# Schematic_F450.net
KiCad netlist of a schematic drawn in Altium Designer
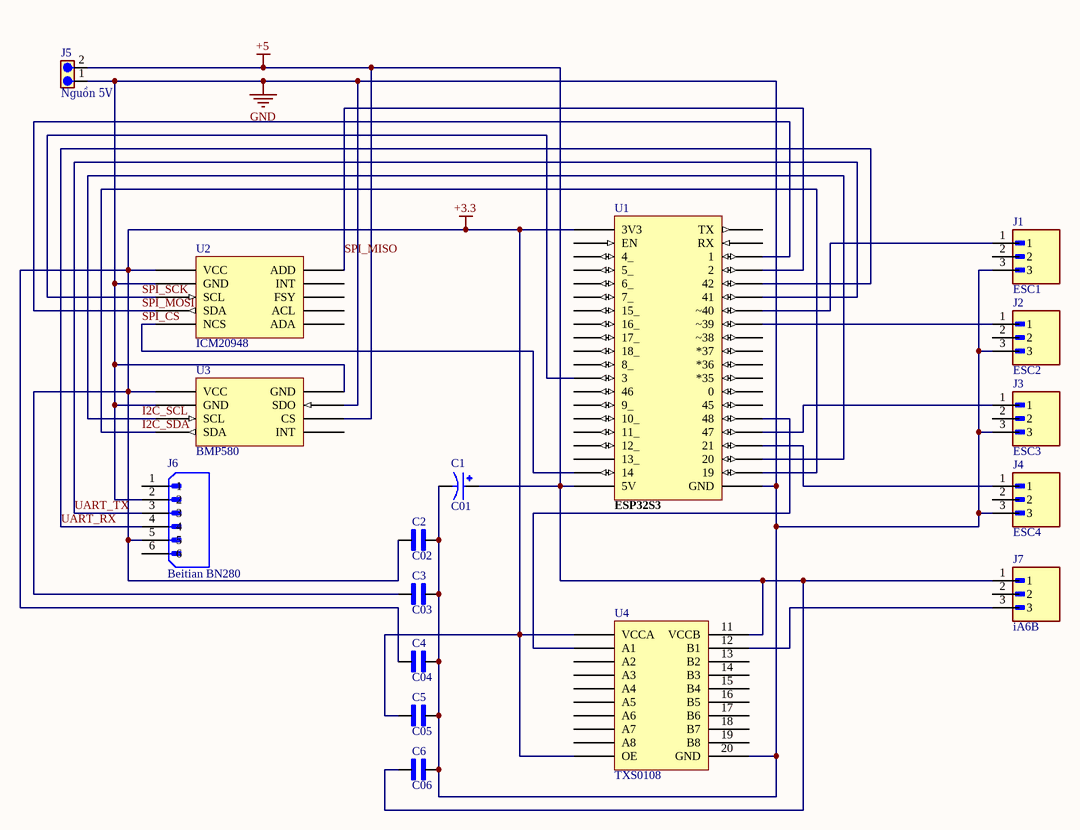
[diagram p0: Schematic F450.SchDoc]

(export (version "E")
  (design (tool "Eeschema 10.0.6"))
  (components
    (comp (ref "C1")
      (value "C01")
      (footprint "CAPPRD500W60D1000H1250")
      (description "CAP ALUM 470UF 20% 25V RADIAL TH")
      (fields (field (name "MP") "EEUFK1E471B") (field (name "MF") "Panasonic"))
      (libsource (lib "Tu Hoa 470uF") (part "EEUFK1E471B"))
    )
    (comp (ref "C2")
      (value "C02")
      (footprint "CAPRR254W54L381T254H466")
      (fields (field (name "MF") "KEMET") (field (name "MP") "C315C104K1R5TA"))
      (libsource (lib "Tu Gom 100nF") (part "C315C104K1R5TA"))
    )
    (comp (ref "C3")
      (value "C03")
      (footprint "CAPRR254W54L381T254H466")
      (fields (field (name "MF") "KEMET") (field (name "MP") "C315C104K1R5TA"))
      (libsource (lib "Tu Gom 100nF") (part "C315C104K1R5TA"))
    )
    (comp (ref "C4")
      (value "C04")
      (footprint "CAPRR254W54L381T254H466")
      (fields (field (name "MF") "KEMET") (field (name "MP") "C315C104K1R5TA"))
      (libsource (lib "Tu Gom 100nF") (part "C315C104K1R5TA"))
    )
    (comp (ref "C5")
      (value "C05")
      (footprint "CAPRR254W54L381T254H466")
      (fields (field (name "MF") "KEMET") (field (name "MP") "C315C104K1R5TA"))
      (libsource (lib "Tu Gom 100nF") (part "C315C104K1R5TA"))
    )
    (comp (ref "C6")
      (value "C06")
      (footprint "CAPRR254W54L381T254H466")
      (fields (field (name "MF") "KEMET") (field (name "MP") "C315C104K1R5TA"))
      (libsource (lib "Tu Gom 100nF") (part "C315C104K1R5TA"))
    )
    (comp (ref "J1")
      (value "ESC1")
      (footprint "WURTH_61300311121")
      (fields (field (name "MP") "61300311121"))
      (libsource (lib "Male3Pin") (part "61300311121"))
    )
    (comp (ref "J2")
      (value "ESC2")
      (footprint "WURTH_61300311121")
      (fields (field (name "MP") "61300311121"))
      (libsource (lib "Male3Pin") (part "61300311121"))
    )
    (comp (ref "J3")
      (value "ESC3")
      (footprint "WURTH_61300311121")
      (fields (field (name "MP") "61300311121"))
      (libsource (lib "Male3Pin") (part "61300311121"))
    )
    (comp (ref "J4")
      (value "ESC4")
      (footprint "WURTH_61300311121")
      (fields (field (name "MP") "61300311121"))
      (libsource (lib "Male3Pin") (part "61300311121"))
    )
    (comp (ref "J5")
      (value "Nguồn 5V")
      (footprint "61300211121")
      (fields (field (name "MF") "{'manufacturer': u'Wurth Electronics'}") (field (name "MP") "61300211121"))
      (libsource (lib "ConnectorMale2Pin") (part "6130XX11121_61300211121"))
    )
    (comp (ref "J6")
      (value "Beitian BN280")
      (footprint "MOLEX_530470610")
      (description "Connector Header Through Hole 6 position 0.049 (1.25mm)")
      (fields (field (name "MF") "Molex") (field (name "MP") "530470610"))
      (libsource (lib "JST 125") (part "530470610"))
    )
    (comp (ref "J7")
      (value "iA6B")
      (footprint "WURTH_61300311121")
      (description "Receiver for FC")
      (fields (field (name "MP") "61300311121"))
      (libsource (lib "Male3Pin") (part "61300311121"))
    )
    (comp (ref "U1")
      (value "ESP32S3")
      (footprint "ESP32S3")
      (libsource (lib "ESP32S3 N16R8") (part "ESP32S3"))
    )
    (comp (ref "U2") (value "ICM20948") (footprint "ICM20948") (libsource (lib "ICM20948") (part "ICM20948")))
    (comp (ref "U3") (value "BMP580") (footprint "BMP580") (libsource (lib "BMP580") (part "BMP580")))
    (comp (ref "U4") (value "TXS0108") (footprint "TXS0108") (libsource (lib "TXS0108") (part "TXS0108")))
  )
  (nets
    (net (code "1") (name "+3.3") (class "Default")
      (node (ref "C2") (pin "1") (pinfunction "1_1") (pintype "passive"))
      (node (ref "C3") (pin "1") (pinfunction "1_1") (pintype "passive"))
      (node (ref "C4") (pin "1") (pinfunction "1_1") (pintype "passive"))
      (node (ref "C5") (pin "1") (pinfunction "1_1") (pintype "passive"))
      (node (ref "J6") (pin "5") (pinfunction "5_5") (pintype "passive"))
      (node (ref "U1") (pin "21") (pinfunction "3V3_21") (pintype "power_in"))
      (node (ref "U2") (pin "1") (pinfunction "VCC_1") (pintype "power_in"))
      (node (ref "U3") (pin "1") (pinfunction "VCC_1") (pintype "power_in"))
      (node (ref "U4") (pin "1") (pinfunction "VCCA_1") (pintype "passive"))
      (node (ref "U4") (pin "10") (pinfunction "OE_10") (pintype "passive"))
    )
    (net (code "2") (name "+5") (class "Default")
      (node (ref "C1") (pin "P") (pinfunction "P_P") (pintype "passive"))
      (node (ref "C6") (pin "1") (pinfunction "1_1") (pintype "passive"))
      (node (ref "J5") (pin "2") (pinfunction "2_2") (pintype "passive"))
      (node (ref "J7") (pin "1") (pinfunction "1_1") (pintype "passive"))
      (node (ref "U1") (pin "40") (pinfunction "5V_40") (pintype "power_in"))
      (node (ref "U3") (pin "7") (pinfunction "CS_7") (pintype "passive"))
      (node (ref "U4") (pin "11") (pinfunction "VCCB_11") (pintype "passive"))
    )
    (net (code "3") (name "/I2C_SCL") (class "Default")
      (node (ref "U1") (pin "18") (pinfunction "20_18") (pintype "bidirectional"))
      (node (ref "U3") (pin "3") (pinfunction "SCL_3") (pintype "input"))
    )
    (net (code "4") (name "/I2C_SDA") (class "Default")
      (node (ref "U1") (pin "19") (pinfunction "19_19") (pintype "bidirectional"))
      (node (ref "U3") (pin "4") (pinfunction "SDA_4") (pintype "output"))
    )
    (net (code "5") (name "/SPI_CS") (class "Default")
      (node (ref "U1") (pin "39") (pinfunction "14_39") (pintype "bidirectional"))
      (node (ref "U2") (pin "5") (pinfunction "NCS_5") (pintype "passive"))
    )
    (net (code "6") (name "/SPI_MISO") (class "Default")
      (node (ref "U1") (pin "4") (pinfunction "2_4") (pintype "bidirectional"))
      (node (ref "U2") (pin "6") (pinfunction "ADD_6") (pintype "passive"))
    )
    (net (code "7") (name "/SPI_MOSI") (class "Default")
      (node (ref "U1") (pin "3") (pinfunction "1_3") (pintype "bidirectional"))
      (node (ref "U2") (pin "4") (pinfunction "SDA_4") (pintype "output"))
    )
    (net (code "8") (name "/SPI_SCK") (class "Default")
      (node (ref "U1") (pin "32") (pinfunction "3_32") (pintype "bidirectional"))
      (node (ref "U2") (pin "3") (pinfunction "SCL_3") (pintype "input"))
    )
    (net (code "9") (name "/UART_RX") (class "Default")
      (node (ref "J6") (pin "4") (pinfunction "4_4") (pintype "passive"))
      (node (ref "U1") (pin "5") (pinfunction "42_5") (pintype "bidirectional"))
    )
    (net (code "10") (name "/UART_TX") (class "Default")
      (node (ref "J6") (pin "3") (pinfunction "3_3") (pintype "passive"))
      (node (ref "U1") (pin "6") (pinfunction "41_6") (pintype "bidirectional"))
    )
    (net (code "11") (name "GND") (class "Default")
      (node (ref "C1") (pin "N") (pinfunction "N_N") (pintype "passive"))
      (node (ref "C2") (pin "2") (pinfunction "2_2") (pintype "passive"))
      (node (ref "C3") (pin "2") (pinfunction "2_2") (pintype "passive"))
      (node (ref "C4") (pin "2") (pinfunction "2_2") (pintype "passive"))
      (node (ref "C5") (pin "2") (pinfunction "2_2") (pintype "passive"))
      (node (ref "C6") (pin "2") (pinfunction "2_2") (pintype "passive"))
      (node (ref "J1") (pin "3") (pinfunction "3_3") (pintype "passive"))
      (node (ref "J2") (pin "3") (pinfunction "3_3") (pintype "passive"))
      (node (ref "J3") (pin "3") (pinfunction "3_3") (pintype "passive"))
      (node (ref "J4") (pin "3") (pinfunction "3_3") (pintype "passive"))
      (node (ref "J5") (pin "1") (pinfunction "1_1") (pintype "passive"))
      (node (ref "J6") (pin "2") (pinfunction "2_2") (pintype "passive"))
      (node (ref "U1") (pin "20") (pinfunction "GND_20") (pintype "power_in"))
      (node (ref "U2") (pin "2") (pinfunction "GND_2") (pintype "power_in"))
      (node (ref "U3") (pin "2") (pinfunction "GND_2") (pintype "power_in"))
      (node (ref "U3") (pin "5") (pinfunction "GND_5") (pintype "power_in"))
      (node (ref "U3") (pin "6") (pinfunction "SDO_6") (pintype "input"))
      (node (ref "U4") (pin "20") (pinfunction "GND_20") (pintype "passive"))
    )
    (net (code "12") (name "Net-(U1-21)") (class "Default")
      (node (ref "J4") (pin "1") (pinfunction "1_1") (pintype "passive"))
      (node (ref "U1") (pin "17") (pinfunction "21_17") (pintype "bidirectional"))
    )
    (net (code "13") (name "Net-(U1-47)") (class "Default")
      (node (ref "J3") (pin "1") (pinfunction "1_1") (pintype "passive"))
      (node (ref "U1") (pin "16") (pinfunction "47_16") (pintype "bidirectional"))
    )
    (net (code "14") (name "Net-(U1-48)") (class "Default")
      (node (ref "U1") (pin "15") (pinfunction "48_15") (pintype "bidirectional"))
      (node (ref "U4") (pin "2") (pinfunction "A1_2") (pintype "passive"))
    )
    (net (code "15") (name "Net-(U1-~39)") (class "Default")
      (node (ref "J2") (pin "1") (pinfunction "1_1") (pintype "passive"))
      (node (ref "U1") (pin "8") (pinfunction "~39_8") (pintype "bidirectional"))
    )
    (net (code "16") (name "Net-(U1-~40)") (class "Default")
      (node (ref "J1") (pin "1") (pinfunction "1_1") (pintype "passive"))
      (node (ref "U1") (pin "7") (pinfunction "~40_7") (pintype "bidirectional"))
    )
    (net (code "17") (name "Net-(U4-B1)") (class "Default")
      (node (ref "J7") (pin "3") (pinfunction "3_3") (pintype "passive"))
      (node (ref "U4") (pin "12") (pinfunction "B1_12") (pintype "passive"))
    )
    (net (code "18") (name "unconnected-(J1-Pad2)") (class "Default")
      (node (ref "J1") (pin "2") (pinfunction "2_2") (pintype "passive"))
    )
    (net (code "19") (name "unconnected-(J2-Pad2)") (class "Default")
      (node (ref "J2") (pin "2") (pinfunction "2_2") (pintype "passive"))
    )
    (net (code "20") (name "unconnected-(J3-Pad2)") (class "Default")
      (node (ref "J3") (pin "2") (pinfunction "2_2") (pintype "passive"))
    )
    (net (code "21") (name "unconnected-(J4-Pad2)") (class "Default")
      (node (ref "J4") (pin "2") (pinfunction "2_2") (pintype "passive"))
    )
    (net (code "22") (name "unconnected-(J6-Pad1)") (class "Default")
      (node (ref "J6") (pin "1") (pinfunction "1_1") (pintype "passive"))
    )
    (net (code "23") (name "unconnected-(J6-Pad6)") (class "Default")
      (node (ref "J6") (pin "6") (pinfunction "6_6") (pintype "passive"))
    )
    (net (code "24") (name "unconnected-(J7-Pad2)") (class "Default")
      (node (ref "J7") (pin "2") (pinfunction "2_2") (pintype "passive"))
    )
    (net (code "25") (name "unconnected-(U1-*35-Pad12)") (class "Default")
      (node (ref "U1") (pin "12") (pinfunction "*35_12") (pintype "bidirectional"))
    )
    (net (code "26") (name "unconnected-(U1-*36-Pad11)") (class "Default")
      (node (ref "U1") (pin "11") (pinfunction "*36_11") (pintype "bidirectional"))
    )
    (net (code "27") (name "unconnected-(U1-*37-Pad10)") (class "Default")
      (node (ref "U1") (pin "10") (pinfunction "*37_10") (pintype "bidirectional"))
    )
    (net (code "28") (name "unconnected-(U1-0-Pad13)") (class "Default")
      (node (ref "U1") (pin "13") (pinfunction "0_13") (pintype "bidirectional"))
    )
    (net (code "29") (name "unconnected-(U1-4_-Pad23)") (class "Default")
      (node (ref "U1") (pin "23") (pinfunction "4__23") (pintype "bidirectional"))
    )
    (net (code "30") (name "unconnected-(U1-5_-Pad24)") (class "Default")
      (node (ref "U1") (pin "24") (pinfunction "5__24") (pintype "bidirectional"))
    )
    (net (code "31") (name "unconnected-(U1-6_-Pad25)") (class "Default")
      (node (ref "U1") (pin "25") (pinfunction "6__25") (pintype "bidirectional"))
    )
    (net (code "32") (name "unconnected-(U1-7_-Pad26)") (class "Default")
      (node (ref "U1") (pin "26") (pinfunction "7__26") (pintype "bidirectional"))
    )
    (net (code "33") (name "unconnected-(U1-8_-Pad31)") (class "Default")
      (node (ref "U1") (pin "31") (pinfunction "8__31") (pintype "bidirectional"))
    )
    (net (code "34") (name "unconnected-(U1-9_-Pad34)") (class "Default")
      (node (ref "U1") (pin "34") (pinfunction "9__34") (pintype "bidirectional"))
    )
    (net (code "35") (name "unconnected-(U1-10_-Pad35)") (class "Default")
      (node (ref "U1") (pin "35") (pinfunction "10__35") (pintype "bidirectional"))
    )
    (net (code "36") (name "unconnected-(U1-11_-Pad36)") (class "Default")
      (node (ref "U1") (pin "36") (pinfunction "11__36") (pintype "bidirectional"))
    )
    (net (code "37") (name "unconnected-(U1-12_-Pad37)") (class "Default")
      (node (ref "U1") (pin "37") (pinfunction "12__37") (pintype "bidirectional"))
    )
    (net (code "38") (name "unconnected-(U1-13_-Pad38)") (class "Default")
      (node (ref "U1") (pin "38") (pinfunction "13__38") (pintype "passive"))
    )
    (net (code "39") (name "unconnected-(U1-15_-Pad27)") (class "Default")
      (node (ref "U1") (pin "27") (pinfunction "15__27") (pintype "bidirectional"))
    )
    (net (code "40") (name "unconnected-(U1-16_-Pad28)") (class "Default")
      (node (ref "U1") (pin "28") (pinfunction "16__28") (pintype "bidirectional"))
    )
    (net (code "41") (name "unconnected-(U1-17_-Pad29)") (class "Default")
      (node (ref "U1") (pin "29") (pinfunction "17__29") (pintype "bidirectional"))
    )
    (net (code "42") (name "unconnected-(U1-18_-Pad30)") (class "Default")
      (node (ref "U1") (pin "30") (pinfunction "18__30") (pintype "bidirectional"))
    )
    (net (code "43") (name "unconnected-(U1-45-Pad14)") (class "Default")
      (node (ref "U1") (pin "14") (pinfunction "45_14") (pintype "bidirectional"))
    )
    (net (code "44") (name "unconnected-(U1-46-Pad33)") (class "Default")
      (node (ref "U1") (pin "33") (pinfunction "46_33") (pintype "bidirectional"))
    )
    (net (code "45") (name "unconnected-(U1-EN-Pad22)") (class "Default")
      (node (ref "U1") (pin "22") (pinfunction "EN_22") (pintype "input"))
    )
    (net (code "46") (name "unconnected-(U1-RX-Pad2)") (class "Default")
      (node (ref "U1") (pin "2") (pinfunction "RX_2") (pintype "input"))
    )
    (net (code "47") (name "unconnected-(U1-TX-Pad1)") (class "Default")
      (node (ref "U1") (pin "1") (pinfunction "TX_1") (pintype "output"))
    )
    (net (code "48") (name "unconnected-(U1-~38-Pad9)") (class "Default")
      (node (ref "U1") (pin "9") (pinfunction "~38_9") (pintype "bidirectional"))
    )
    (net (code "49") (name "unconnected-(U2-ACL-Pad9)") (class "Default")
      (node (ref "U2") (pin "9") (pinfunction "ACL_9") (pintype "passive"))
    )
    (net (code "50") (name "unconnected-(U2-ADA-Pad10)") (class "Default")
      (node (ref "U2") (pin "10") (pinfunction "ADA_10") (pintype "passive"))
    )
    (net (code "51") (name "unconnected-(U2-FSY-Pad8)") (class "Default")
      (node (ref "U2") (pin "8") (pinfunction "FSY_8") (pintype "passive"))
    )
    (net (code "52") (name "unconnected-(U2-INT-Pad7)") (class "Default")
      (node (ref "U2") (pin "7") (pinfunction "INT_7") (pintype "passive"))
    )
    (net (code "53") (name "unconnected-(U3-INT-Pad8)") (class "Default")
      (node (ref "U3") (pin "8") (pinfunction "INT_8") (pintype "passive"))
    )
    (net (code "54") (name "unconnected-(U4-A2-Pad3)") (class "Default")
      (node (ref "U4") (pin "3") (pinfunction "A2_3") (pintype "passive"))
    )
    (net (code "55") (name "unconnected-(U4-A3-Pad4)") (class "Default")
      (node (ref "U4") (pin "4") (pinfunction "A3_4") (pintype "passive"))
    )
    (net (code "56") (name "unconnected-(U4-A4-Pad5)") (class "Default")
      (node (ref "U4") (pin "5") (pinfunction "A4_5") (pintype "passive"))
    )
    (net (code "57") (name "unconnected-(U4-A5-Pad6)") (class "Default")
      (node (ref "U4") (pin "6") (pinfunction "A5_6") (pintype "passive"))
    )
    (net (code "58") (name "unconnected-(U4-A6-Pad7)") (class "Default")
      (node (ref "U4") (pin "7") (pinfunction "A6_7") (pintype "passive"))
    )
    (net (code "59") (name "unconnected-(U4-A7-Pad8)") (class "Default")
      (node (ref "U4") (pin "8") (pinfunction "A7_8") (pintype "passive"))
    )
    (net (code "60") (name "unconnected-(U4-A8-Pad9)") (class "Default")
      (node (ref "U4") (pin "9") (pinfunction "A8_9") (pintype "passive"))
    )
    (net (code "61") (name "unconnected-(U4-B2-Pad13)") (class "Default")
      (node (ref "U4") (pin "13") (pinfunction "B2_13") (pintype "passive"))
    )
    (net (code "62") (name "unconnected-(U4-B3-Pad14)") (class "Default")
      (node (ref "U4") (pin "14") (pinfunction "B3_14") (pintype "passive"))
    )
    (net (code "63") (name "unconnected-(U4-B4-Pad15)") (class "Default")
      (node (ref "U4") (pin "15") (pinfunction "B4_15") (pintype "passive"))
    )
    (net (code "64") (name "unconnected-(U4-B5-Pad16)") (class "Default")
      (node (ref "U4") (pin "16") (pinfunction "B5_16") (pintype "passive"))
    )
    (net (code "65") (name "unconnected-(U4-B6-Pad17)") (class "Default")
      (node (ref "U4") (pin "17") (pinfunction "B6_17") (pintype "passive"))
    )
    (net (code "66") (name "unconnected-(U4-B7-Pad18)") (class "Default")
      (node (ref "U4") (pin "18") (pinfunction "B7_18") (pintype "passive"))
    )
    (net (code "67") (name "unconnected-(U4-B8-Pad19)") (class "Default")
      (node (ref "U4") (pin "19") (pinfunction "B8_19") (pintype "passive"))
    )
  )
)
